# receiver_and_power_min_version.net
KiCad netlist of a schematic drawn in EAGLE
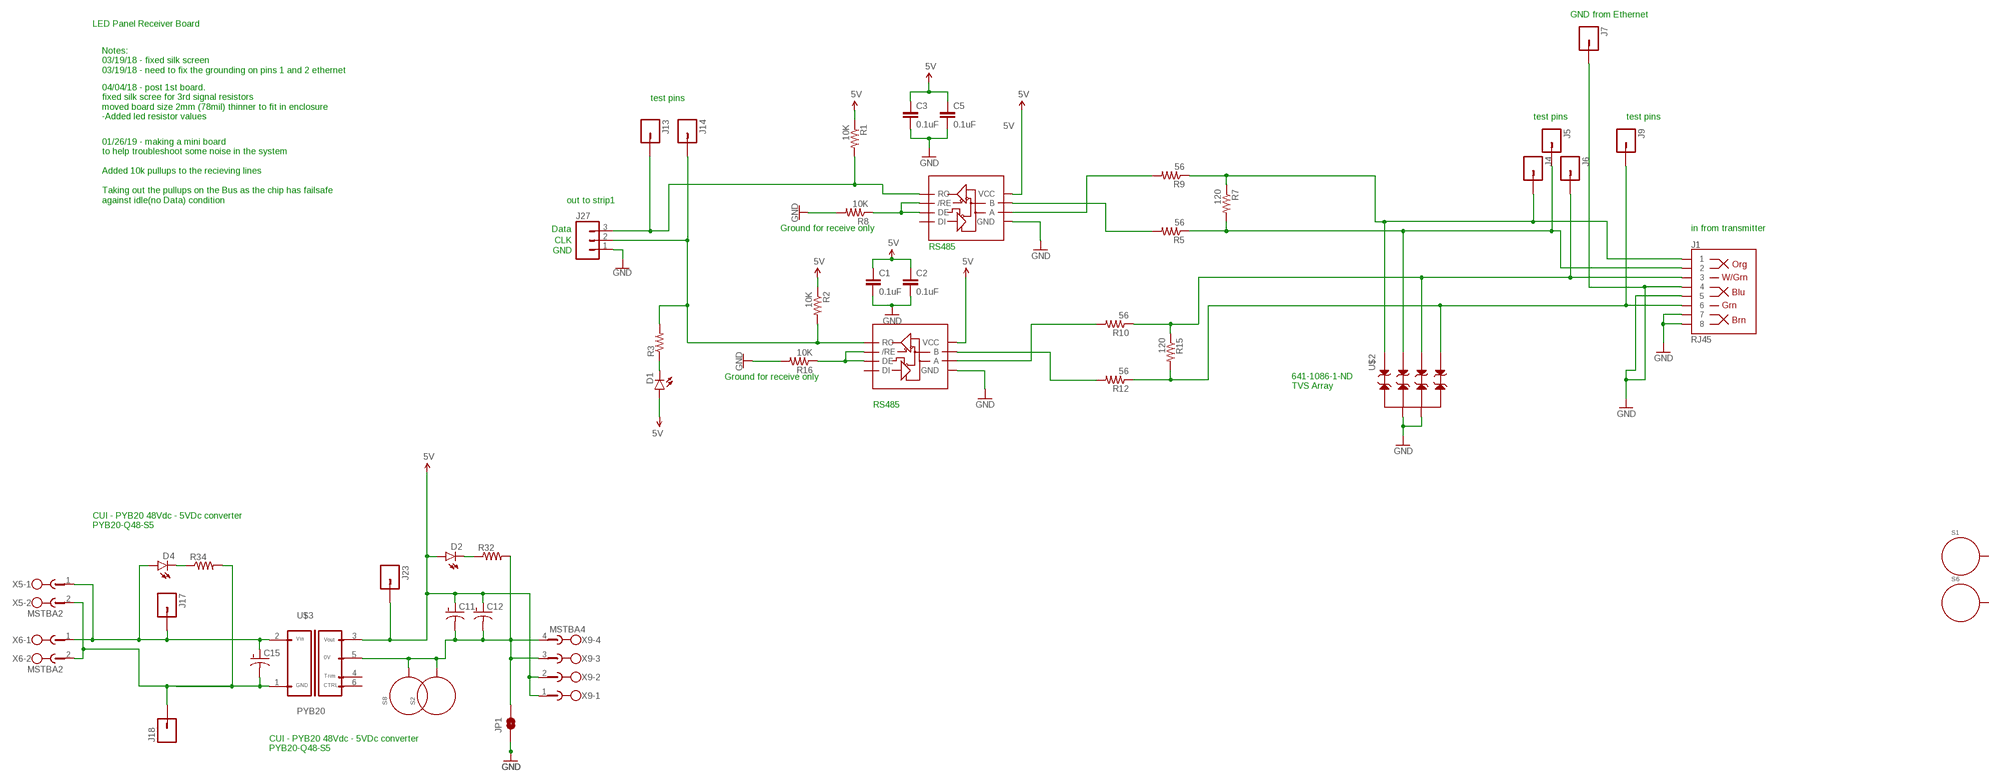
[diagram p0: schematic, sheet 1]

(export (version "E")
  (design (tool "Eeschema 10.0.6"))
  (components
    (comp (ref "C1")
      (value "0.1uF")
      (footprint "eagle-import:0805")
      (libsource (lib "eagle-import") (part "CAP0805"))
    )
    (comp (ref "C2")
      (value "0.1uF")
      (footprint "eagle-import:0805")
      (libsource (lib "eagle-import") (part "CAP0805"))
    )
    (comp (ref "C3")
      (value "0.1uF")
      (footprint "eagle-import:0805")
      (libsource (lib "eagle-import") (part "CAP0805"))
    )
    (comp (ref "C5")
      (value "0.1uF")
      (footprint "eagle-import:0805")
      (libsource (lib "eagle-import") (part "CAP0805"))
    )
    (comp (ref "C11")
      (value "CAP_POLPTH4")
      (footprint "eagle-import:CPOL-RADIAL-1000UF-25V")
      (libsource (lib "eagle-import") (part "SparkFun-Passives_CAP_POLPTH4"))
    )
    (comp (ref "C12")
      (value "CAP_POLPTH4")
      (footprint "eagle-import:CPOL-RADIAL-1000UF-25V")
      (libsource (lib "eagle-import") (part "SparkFun-Passives_CAP_POLPTH4"))
    )
    (comp (ref "C15")
      (value "CAP_POLPTH4")
      (footprint "eagle-import:CPOL-RADIAL-1000UF-25V")
      (libsource (lib "eagle-import") (part "CAP_POLPTH4"))
    )
    (comp (ref "D1")
      (value "LED3MM")
      (footprint "eagle-import:LED3MM")
      (libsource (lib "eagle-import") (part "LED3MM"))
    )
    (comp (ref "D2")
      (value "LED3MM")
      (footprint "eagle-import:LED3MM")
      (libsource (lib "eagle-import") (part "LED3MM"))
    )
    (comp (ref "D4")
      (value "LED3MM")
      (footprint "eagle-import:LED3MM")
      (libsource (lib "eagle-import") (part "LED3MM"))
    )
    (comp (ref "J1")
      (value "RJ45")
      (footprint "eagle-import:RJ45-8")
      (libsource (lib "eagle-import") (part "RJ45-8"))
    )
    (comp (ref "J4")
      (value "M01PTH")
      (footprint "eagle-import:1X01")
      (libsource (lib "eagle-import") (part "M01PTH"))
    )
    (comp (ref "J5")
      (value "M01PTH")
      (footprint "eagle-import:1X01")
      (libsource (lib "eagle-import") (part "M01PTH"))
    )
    (comp (ref "J6")
      (value "M01PTH")
      (footprint "eagle-import:1X01")
      (libsource (lib "eagle-import") (part "M01PTH"))
    )
    (comp (ref "J7")
      (value "M01PTH")
      (footprint "eagle-import:1X01")
      (libsource (lib "eagle-import") (part "M01PTH"))
    )
    (comp (ref "J9")
      (value "M01PTH")
      (footprint "eagle-import:1X01")
      (libsource (lib "eagle-import") (part "M01PTH"))
    )
    (comp (ref "J13")
      (value "M01PTH")
      (footprint "eagle-import:1X01")
      (libsource (lib "eagle-import") (part "M01PTH"))
    )
    (comp (ref "J14")
      (value "M01PTH")
      (footprint "eagle-import:1X01")
      (libsource (lib "eagle-import") (part "M01PTH"))
    )
    (comp (ref "J17")
      (value "M01PTH")
      (footprint "eagle-import:1X01")
      (libsource (lib "eagle-import") (part "M01PTH"))
    )
    (comp (ref "J18")
      (value "M01PTH")
      (footprint "eagle-import:1X01")
      (libsource (lib "eagle-import") (part "M01PTH"))
    )
    (comp (ref "J23")
      (value "M01PTH")
      (footprint "eagle-import:1X01")
      (libsource (lib "eagle-import") (part "M01PTH"))
    )
    (comp (ref "J27")
      (value "M03SCREW")
      (footprint "eagle-import:SCREWTERMINAL-3.5MM-3")
      (libsource (lib "eagle-import") (part "M03SCREW"))
    )
    (comp (ref "JP1")
      (value "JUMPER-PAD-2-NC_BY_TRACE")
      (footprint "eagle-import:PAD-JUMPER-2-NC_BY_TRACE_YES_SILK")
      (libsource (lib "eagle-import") (part "JUMPER-PAD-2-NC_BY_TRACE"))
    )
    (comp (ref "R1")
      (value "10K")
      (footprint "eagle-import:0805")
      (libsource (lib "eagle-import") (part "RESISTOR0805-RES"))
    )
    (comp (ref "R2")
      (value "10K")
      (footprint "eagle-import:0805")
      (libsource (lib "eagle-import") (part "RESISTOR0805-RES"))
    )
    (comp (ref "R3")
      (value "RESISTOR0805-RES")
      (footprint "eagle-import:0805")
      (libsource (lib "eagle-import") (part "SparkFun-Passives_RESISTOR0805-RES"))
    )
    (comp (ref "R5")
      (value "56")
      (footprint "eagle-import:0805")
      (libsource (lib "eagle-import") (part "RESISTOR0805-RES"))
    )
    (comp (ref "R7")
      (value "120")
      (footprint "eagle-import:0805")
      (libsource (lib "eagle-import") (part "RESISTOR0805-RES"))
    )
    (comp (ref "R8")
      (value "10K")
      (footprint "eagle-import:0805")
      (libsource (lib "eagle-import") (part "RESISTOR0805-RES"))
    )
    (comp (ref "R9")
      (value "56")
      (footprint "eagle-import:0805")
      (libsource (lib "eagle-import") (part "RESISTOR0805-RES"))
    )
    (comp (ref "R10")
      (value "56")
      (footprint "eagle-import:0805")
      (libsource (lib "eagle-import") (part "RESISTOR0805-RES"))
    )
    (comp (ref "R12")
      (value "56")
      (footprint "eagle-import:0805")
      (libsource (lib "eagle-import") (part "RESISTOR0805-RES"))
    )
    (comp (ref "R15")
      (value "120")
      (footprint "eagle-import:0805")
      (libsource (lib "eagle-import") (part "RESISTOR0805-RES"))
    )
    (comp (ref "R16")
      (value "10K")
      (footprint "eagle-import:0805")
      (libsource (lib "eagle-import") (part "RESISTOR0805-RES"))
    )
    (comp (ref "R32")
      (value "RESISTORPTH-1/4W")
      (footprint "eagle-import:AXIAL-0.4")
      (libsource (lib "eagle-import") (part "SparkFun-Passives_RESISTORPTH-1/4W"))
    )
    (comp (ref "R34")
      (value "RESISTORPTH-1/4W")
      (footprint "eagle-import:AXIAL-0.4")
      (libsource (lib "eagle-import") (part "SparkFun-Passives_RESISTORPTH-1/4W"))
    )
    (comp (ref "S1")
      (value "STANDOFF_ELECTRICAL5-32")
      (footprint "eagle-import:STANDOFF_ELECTRICAL_5_32")
      (libsource (lib "eagle-import") (part "STANDOFF_ELECTRICAL5-32"))
    )
    (comp (ref "S2")
      (value "STANDOFF_ELECTRICAL5-32")
      (footprint "eagle-import:STANDOFF_ELECTRICAL_5_32")
      (libsource (lib "eagle-import") (part "STANDOFF_ELECTRICAL5-32"))
    )
    (comp (ref "S6")
      (value "STANDOFF_ELECTRICAL5-32")
      (footprint "eagle-import:STANDOFF_ELECTRICAL_5_32")
      (libsource (lib "eagle-import") (part "STANDOFF_ELECTRICAL5-32"))
    )
    (comp (ref "S8")
      (value "STANDOFF_ELECTRICAL5-32")
      (footprint "eagle-import:STANDOFF_ELECTRICAL_5_32")
      (libsource (lib "eagle-import") (part "STANDOFF_ELECTRICAL5-32"))
    )
    (comp (ref "U$2")
      (value "TVS_ARRAY")
      (footprint "eagle-import:SOT26")
      (libsource (lib "eagle-import") (part "TVS_ARRAY"))
    )
    (comp (ref "U$3")
      (value "PYB20")
      (footprint "eagle-import:CUI_PYB20_PCB_DC_DC")
      (libsource (lib "eagle-import") (part "PYB20"))
    )
    (comp (ref "U1")
      (value "ST1480ACSOIC")
      (footprint "eagle-import:SO08")
      (libsource (lib "eagle-import") (part "ST1480ACSOIC"))
    )
    (comp (ref "U2")
      (value "ST1480ACSOIC")
      (footprint "eagle-import:SO08")
      (libsource (lib "eagle-import") (part "ST1480ACSOIC"))
    )
    (comp (ref "X5")
      (value "MSTBA2")
      (footprint "eagle-import:MSTBA2")
      (fields (field (name "MF") "FARNELL") (field (name "MPN") "1757242"))
      (libsource (lib "eagle-import") (part "MSTBA2"))
    )
    (comp (ref "X6")
      (value "MSTBA2")
      (footprint "eagle-import:MSTBA2")
      (fields (field (name "MF") "FARNELL") (field (name "MPN") "1757242"))
      (libsource (lib "eagle-import") (part "MSTBA2"))
    )
    (comp (ref "X9")
      (value "MSTBA4")
      (footprint "eagle-import:MSTBA4")
      (fields (field (name "MF") "FARNELL") (field (name "MPN") "1757268"))
      (libsource (lib "eagle-import") (part "MSTBA4"))
    )
  )
  (nets
    (net (code "1") (name "5V") (class "Default")
      (node (ref "C1") (pin "1") (pinfunction "1_1") (pintype "passive"))
      (node (ref "C11") (pin "1") (pinfunction "+_1") (pintype "passive"))
      (node (ref "C12") (pin "1") (pinfunction "+_1") (pintype "passive"))
      (node (ref "C2") (pin "1") (pinfunction "1_1") (pintype "passive"))
      (node (ref "C3") (pin "1") (pinfunction "1_1") (pintype "passive"))
      (node (ref "C5") (pin "1") (pinfunction "1_1") (pintype "passive"))
      (node (ref "D1") (pin "A") (pinfunction "A_A") (pintype "passive"))
      (node (ref "D2") (pin "A") (pinfunction "A_A") (pintype "passive"))
      (node (ref "J23") (pin "1") (pinfunction "1_1") (pintype "passive"))
      (node (ref "R1") (pin "1") (pinfunction "1_1") (pintype "passive"))
      (node (ref "R2") (pin "1") (pinfunction "1_1") (pintype "passive"))
      (node (ref "U$3") (pin "3") (pinfunction "V+_3") (pintype "passive"))
      (node (ref "U1") (pin "8") (pinfunction "VCC_8") (pintype "bidirectional"))
      (node (ref "U2") (pin "8") (pinfunction "VCC_8") (pintype "bidirectional"))
      (node (ref "X9") (pin "1") (pinfunction "1_1") (pintype "passive"))
      (node (ref "X9") (pin "2") (pinfunction "1_2") (pintype "passive"))
    )
    (net (code "2") (name "GND") (class "Default")
      (node (ref "C1") (pin "2") (pinfunction "2_2") (pintype "passive"))
      (node (ref "C2") (pin "2") (pinfunction "2_2") (pintype "passive"))
      (node (ref "C3") (pin "2") (pinfunction "2_2") (pintype "passive"))
      (node (ref "C5") (pin "2") (pinfunction "2_2") (pintype "passive"))
      (node (ref "J1") (pin "4") (pinfunction "4_4") (pintype "bidirectional"))
      (node (ref "J1") (pin "5") (pinfunction "5_5") (pintype "bidirectional"))
      (node (ref "J1") (pin "7") (pinfunction "7_7") (pintype "bidirectional"))
      (node (ref "J1") (pin "8") (pinfunction "8_8") (pintype "bidirectional"))
      (node (ref "J27") (pin "1") (pinfunction "1_1") (pintype "passive"))
      (node (ref "J7") (pin "1") (pinfunction "1_1") (pintype "passive"))
      (node (ref "JP1") (pin "1") (pinfunction "1_1") (pintype "passive"))
      (node (ref "R16") (pin "2") (pinfunction "2_2") (pintype "passive"))
      (node (ref "R8") (pin "2") (pinfunction "2_2") (pintype "passive"))
      (node (ref "U$2") (pin "2") (pinfunction "2_2") (pintype "passive"))
      (node (ref "U$2") (pin "5") (pinfunction "5_5") (pintype "passive"))
      (node (ref "U1") (pin "5") (pinfunction "GND_5") (pintype "bidirectional"))
      (node (ref "U2") (pin "5") (pinfunction "GND_5") (pintype "bidirectional"))
    )
    (net (code "3") (name "Net-(C11--)") (class "Default")
      (node (ref "C11") (pin "2") (pinfunction "-_2") (pintype "passive"))
      (node (ref "C12") (pin "2") (pinfunction "-_2") (pintype "passive"))
      (node (ref "JP1") (pin "2") (pinfunction "2_2") (pintype "passive"))
      (node (ref "R32") (pin "P$2") (pinfunction "2_P$2") (pintype "passive"))
      (node (ref "S2") (pin "P1") (pinfunction "P$1_P1") (pintype "bidirectional"))
      (node (ref "S8") (pin "P1") (pinfunction "P$1_P1") (pintype "bidirectional"))
      (node (ref "U$3") (pin "5") (pinfunction "0V_5") (pintype "passive"))
      (node (ref "X9") (pin "3") (pinfunction "1_3") (pintype "passive"))
      (node (ref "X9") (pin "4") (pinfunction "1_4") (pintype "passive"))
    )
    (net (code "4") (name "Net-(D1-C)") (class "Default")
      (node (ref "D1") (pin "K") (pinfunction "C_K") (pintype "passive"))
      (node (ref "R3") (pin "1") (pinfunction "1_1") (pintype "passive"))
    )
    (net (code "5") (name "Net-(D2-C)") (class "Default")
      (node (ref "D2") (pin "K") (pinfunction "C_K") (pintype "passive"))
      (node (ref "R32") (pin "P$1") (pinfunction "1_P$1") (pintype "passive"))
    )
    (net (code "6") (name "Net-(D4-C)") (class "Default")
      (node (ref "D4") (pin "K") (pinfunction "C_K") (pintype "passive"))
      (node (ref "R34") (pin "P$1") (pinfunction "1_P$1") (pintype "passive"))
    )
    (net (code "7") (name "Net-(J1-Pad1)") (class "Default")
      (node (ref "J1") (pin "1") (pinfunction "1_1") (pintype "bidirectional"))
      (node (ref "J4") (pin "1") (pinfunction "1_1") (pintype "passive"))
      (node (ref "R7") (pin "1") (pinfunction "1_1") (pintype "passive"))
      (node (ref "R9") (pin "1") (pinfunction "1_1") (pintype "passive"))
      (node (ref "U$2") (pin "1") (pinfunction "1_1") (pintype "passive"))
    )
    (net (code "8") (name "Net-(J1-Pad2)") (class "Default")
      (node (ref "J1") (pin "2") (pinfunction "2_2") (pintype "bidirectional"))
      (node (ref "J5") (pin "1") (pinfunction "1_1") (pintype "passive"))
      (node (ref "R5") (pin "1") (pinfunction "1_1") (pintype "passive"))
      (node (ref "R7") (pin "2") (pinfunction "2_2") (pintype "passive"))
      (node (ref "U$2") (pin "3") (pinfunction "3_3") (pintype "passive"))
    )
    (net (code "9") (name "Net-(J1-Pad3)") (class "Default")
      (node (ref "J1") (pin "3") (pinfunction "3_3") (pintype "bidirectional"))
      (node (ref "J6") (pin "1") (pinfunction "1_1") (pintype "passive"))
      (node (ref "R10") (pin "1") (pinfunction "1_1") (pintype "passive"))
      (node (ref "R15") (pin "1") (pinfunction "1_1") (pintype "passive"))
      (node (ref "U$2") (pin "4") (pinfunction "4_4") (pintype "passive"))
    )
    (net (code "10") (name "Net-(J1-Pad6)") (class "Default")
      (node (ref "J1") (pin "6") (pinfunction "6_6") (pintype "bidirectional"))
      (node (ref "J9") (pin "1") (pinfunction "1_1") (pintype "passive"))
      (node (ref "R12") (pin "1") (pinfunction "1_1") (pintype "passive"))
      (node (ref "R15") (pin "2") (pinfunction "2_2") (pintype "passive"))
      (node (ref "U$2") (pin "6") (pinfunction "6_6") (pintype "passive"))
    )
    (net (code "11") (name "Net-(R34-2)") (class "Default")
      (node (ref "C15") (pin "-") (pinfunction "-_-") (pintype "passive"))
      (node (ref "J18") (pin "1") (pinfunction "1_1") (pintype "passive"))
      (node (ref "R34") (pin "P$2") (pinfunction "2_P$2") (pintype "passive"))
      (node (ref "U$3") (pin "1") (pinfunction "GND1_1") (pintype "passive"))
      (node (ref "X5") (pin "2") (pinfunction "1_2") (pintype "passive"))
      (node (ref "X6") (pin "2") (pinfunction "1_2") (pintype "passive"))
    )
    (net (code "12") (name "Net-(U$3-VIN)") (class "Default")
      (node (ref "C15") (pin "+") (pinfunction "+_+") (pintype "passive"))
      (node (ref "D4") (pin "A") (pinfunction "A_A") (pintype "passive"))
      (node (ref "J17") (pin "1") (pinfunction "1_1") (pintype "passive"))
      (node (ref "U$3") (pin "2") (pinfunction "VIN_2") (pintype "passive"))
      (node (ref "X5") (pin "1") (pinfunction "1_1") (pintype "passive"))
      (node (ref "X6") (pin "1") (pinfunction "1_1") (pintype "passive"))
    )
    (net (code "13") (name "Net-(U1-A)") (class "Default")
      (node (ref "R9") (pin "2") (pinfunction "2_2") (pintype "passive"))
      (node (ref "U1") (pin "6") (pinfunction "A_6") (pintype "bidirectional"))
    )
    (net (code "14") (name "Net-(U1-B)") (class "Default")
      (node (ref "R5") (pin "2") (pinfunction "2_2") (pintype "passive"))
      (node (ref "U1") (pin "7") (pinfunction "B_7") (pintype "bidirectional"))
    )
    (net (code "15") (name "Net-(U1-DE)") (class "Default")
      (node (ref "R8") (pin "1") (pinfunction "1_1") (pintype "passive"))
      (node (ref "U1") (pin "2") (pinfunction "/RE_2") (pintype "bidirectional"))
      (node (ref "U1") (pin "3") (pinfunction "DE_3") (pintype "bidirectional"))
    )
    (net (code "16") (name "Net-(U1-RO)") (class "Default")
      (node (ref "J13") (pin "1") (pinfunction "1_1") (pintype "passive"))
      (node (ref "J27") (pin "3") (pinfunction "3_3") (pintype "passive"))
      (node (ref "R1") (pin "2") (pinfunction "2_2") (pintype "passive"))
      (node (ref "U1") (pin "1") (pinfunction "RO_1") (pintype "bidirectional"))
    )
    (net (code "17") (name "Net-(U2-A)") (class "Default")
      (node (ref "R10") (pin "2") (pinfunction "2_2") (pintype "passive"))
      (node (ref "U2") (pin "6") (pinfunction "A_6") (pintype "bidirectional"))
    )
    (net (code "18") (name "Net-(U2-B)") (class "Default")
      (node (ref "R12") (pin "2") (pinfunction "2_2") (pintype "passive"))
      (node (ref "U2") (pin "7") (pinfunction "B_7") (pintype "bidirectional"))
    )
    (net (code "19") (name "Net-(U2-DE)") (class "Default")
      (node (ref "R16") (pin "1") (pinfunction "1_1") (pintype "passive"))
      (node (ref "U2") (pin "2") (pinfunction "/RE_2") (pintype "bidirectional"))
      (node (ref "U2") (pin "3") (pinfunction "DE_3") (pintype "bidirectional"))
    )
    (net (code "20") (name "Net-(U2-RO)") (class "Default")
      (node (ref "J14") (pin "1") (pinfunction "1_1") (pintype "passive"))
      (node (ref "J27") (pin "2") (pinfunction "2_2") (pintype "passive"))
      (node (ref "R2") (pin "2") (pinfunction "2_2") (pintype "passive"))
      (node (ref "R3") (pin "2") (pinfunction "2_2") (pintype "passive"))
      (node (ref "U2") (pin "1") (pinfunction "RO_1") (pintype "bidirectional"))
    )
    (net (code "21") (name "unconnected-(S1-P$1-PadP1)") (class "Default")
      (node (ref "S1") (pin "P1") (pinfunction "P$1_P1") (pintype "bidirectional"))
    )
    (net (code "22") (name "unconnected-(S6-P$1-PadP1)") (class "Default")
      (node (ref "S6") (pin "P1") (pinfunction "P$1_P1") (pintype "bidirectional"))
    )
    (net (code "23") (name "unconnected-(U$3-CTRL-Pad6)") (class "Default")
      (node (ref "U$3") (pin "6") (pinfunction "CTRL_6") (pintype "passive"))
    )
    (net (code "24") (name "unconnected-(U$3-TRIM-Pad4)") (class "Default")
      (node (ref "U$3") (pin "4") (pinfunction "TRIM_4") (pintype "passive"))
    )
    (net (code "25") (name "unconnected-(U1-DI-Pad4)") (class "Default")
      (node (ref "U1") (pin "4") (pinfunction "DI_4") (pintype "bidirectional"))
    )
    (net (code "26") (name "unconnected-(U2-DI-Pad4)") (class "Default")
      (node (ref "U2") (pin "4") (pinfunction "DI_4") (pintype "bidirectional"))
    )
  )
)
